# JustStupid.net
KiCad netlist of a schematic drawn in EAGLE
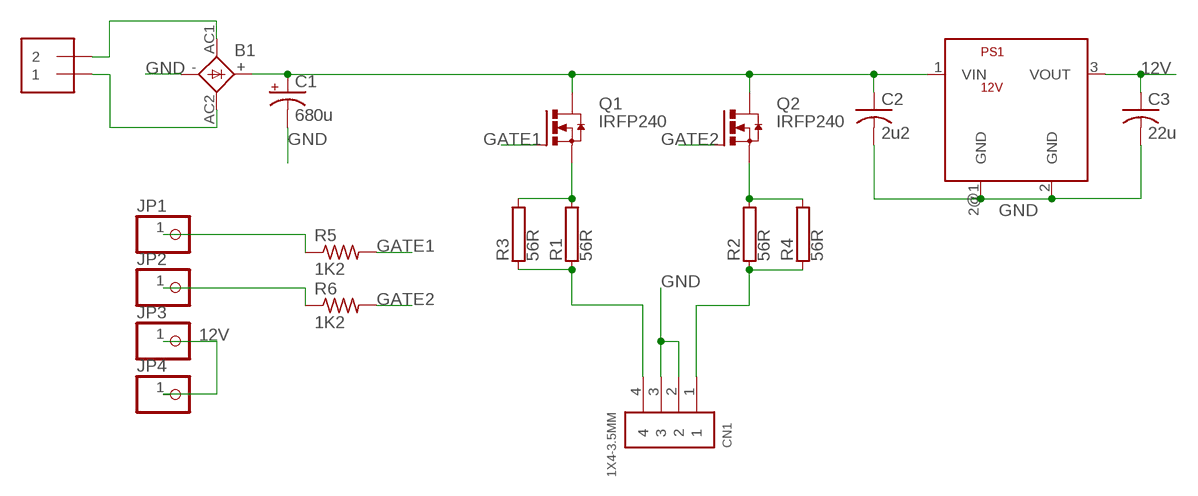
[diagram p0: schematic, sheet 1]

(export (version "E")
  (design (tool "Eeschema 10.0.6"))
  (components
    (comp (ref "ACIN")
      (value "1X2-3.5MM")
      (footprint "eagle-import:1X2-3.5MM")
      (libsource (lib "eagle-import") (part "1X2-3.5MM"))
    )
    (comp (ref "B1")
      (value "KBU")
      (footprint "eagle-import:KBU")
      (libsource (lib "eagle-import") (part "KBU"))
    )
    (comp (ref "C1")
      (value "680u")
      (footprint "eagle-import:PCPIN_CAP")
      (libsource (lib "eagle-import") (part "C_POL"))
    )
    (comp (ref "C2")
      (value "2u2")
      (footprint "eagle-import:C2220K")
      (libsource (lib "eagle-import") (part "C-USC2220K"))
    )
    (comp (ref "C3")
      (value "22u")
      (footprint "eagle-import:C1206")
      (libsource (lib "eagle-import") (part "C-USC1206"))
    )
    (comp (ref "CN1")
      (value "1X4-3.5MM")
      (footprint "eagle-import:1X04-3.5MM")
      (libsource (lib "eagle-import") (part "1X4-3.5MM"))
    )
    (comp (ref "JP1")
      (value "PINHD-1X1")
      (footprint "eagle-import:1X01")
      (libsource (lib "eagle-import") (part "PINHD-1X1"))
    )
    (comp (ref "JP2")
      (value "PINHD-1X1")
      (footprint "eagle-import:1X01")
      (libsource (lib "eagle-import") (part "PINHD-1X1"))
    )
    (comp (ref "JP3")
      (value "PINHD-1X1")
      (footprint "eagle-import:1X01")
      (libsource (lib "eagle-import") (part "PINHD-1X1"))
    )
    (comp (ref "JP4")
      (value "PINHD-1X1")
      (footprint "eagle-import:1X01")
      (libsource (lib "eagle-import") (part "PINHD-1X1"))
    )
    (comp (ref "PS1")
      (value "12V")
      (footprint "eagle-import:SOT89")
      (libsource (lib "eagle-import") (part "NCP785A"))
    )
    (comp (ref "Q1")
      (value "IRFP240")
      (footprint "eagle-import:TO247BV")
      (libsource (lib "eagle-import") (part "IRFP240"))
    )
    (comp (ref "Q2")
      (value "IRFP240")
      (footprint "eagle-import:TO247BV")
      (libsource (lib "eagle-import") (part "IRFP240"))
    )
    (comp (ref "R1")
      (value "56R")
      (footprint "eagle-import:TO-247-2V")
      (libsource (lib "eagle-import") (part "RMG100-V"))
    )
    (comp (ref "R2")
      (value "56R")
      (footprint "eagle-import:TO-247-2V")
      (libsource (lib "eagle-import") (part "RMG100-V"))
    )
    (comp (ref "R3")
      (value "56R")
      (footprint "eagle-import:TO-247-2V")
      (libsource (lib "eagle-import") (part "RMG100-V"))
    )
    (comp (ref "R4")
      (value "56R")
      (footprint "eagle-import:TO-247-2V")
      (libsource (lib "eagle-import") (part "RMG100-V"))
    )
    (comp (ref "R5")
      (value "1K2")
      (footprint "eagle-import:R1206")
      (libsource (lib "eagle-import") (part "R-US_R1206"))
    )
    (comp (ref "R6")
      (value "1K2")
      (footprint "eagle-import:R1206")
      (libsource (lib "eagle-import") (part "R-US_R1206"))
    )
  )
  (nets
    (net (code "1") (name "/12V") (class "Default")
      (node (ref "C3") (pin "1") (pinfunction "1_1") (pintype "passive"))
      (node (ref "JP3") (pin "1") (pinfunction "1_1") (pintype "passive"))
      (node (ref "JP4") (pin "1") (pinfunction "1_1") (pintype "passive"))
      (node (ref "PS1") (pin "3") (pinfunction "VOUT_3") (pintype "bidirectional"))
    )
    (net (code "2") (name "/GATE1") (class "Default")
      (node (ref "Q1") (pin "G") (pinfunction "G_G") (pintype "passive"))
      (node (ref "R5") (pin "2") (pinfunction "2_2") (pintype "passive"))
    )
    (net (code "3") (name "/GATE2") (class "Default")
      (node (ref "Q2") (pin "G") (pinfunction "G_G") (pintype "passive"))
      (node (ref "R6") (pin "2") (pinfunction "2_2") (pintype "passive"))
    )
    (net (code "4") (name "/GND") (class "Default")
      (node (ref "B1") (pin "-") (pinfunction "-_-") (pintype "passive"))
      (node (ref "C1") (pin "P$1") (pinfunction "-_P$1") (pintype "passive"))
      (node (ref "C2") (pin "2") (pinfunction "2_2") (pintype "passive"))
      (node (ref "C3") (pin "2") (pinfunction "2_2") (pintype "passive"))
      (node (ref "CN1") (pin "2") (pinfunction "2_2") (pintype "bidirectional"))
      (node (ref "CN1") (pin "3") (pinfunction "3_3") (pintype "bidirectional"))
      (node (ref "PS1") (pin "2") (pinfunction "GND_2") (pintype "bidirectional"))
      (node (ref "PS1") (pin "2@1") (pinfunction "GND_2@1") (pintype "bidirectional"))
    )
    (net (code "5") (name "Net-(ACIN-Pad1)") (class "Default")
      (node (ref "ACIN") (pin "1") (pinfunction "1_1") (pintype "passive"))
      (node (ref "B1") (pin "AC2") (pinfunction "AC2_AC2") (pintype "passive"))
    )
    (net (code "6") (name "Net-(ACIN-Pad2)") (class "Default")
      (node (ref "ACIN") (pin "2") (pinfunction "2_2") (pintype "passive"))
      (node (ref "B1") (pin "AC1") (pinfunction "AC1_AC1") (pintype "passive"))
    )
    (net (code "7") (name "Net-(C1-+)") (class "Default")
      (node (ref "B1") (pin "+") (pinfunction "+_+") (pintype "passive"))
      (node (ref "C1") (pin "P$2") (pinfunction "+_P$2") (pintype "passive"))
      (node (ref "C2") (pin "1") (pinfunction "1_1") (pintype "passive"))
      (node (ref "PS1") (pin "1") (pinfunction "VIN_1") (pintype "bidirectional"))
      (node (ref "Q1") (pin "D") (pinfunction "D_D") (pintype "passive"))
      (node (ref "Q2") (pin "D") (pinfunction "D_D") (pintype "passive"))
    )
    (net (code "8") (name "Net-(CN1-Pad1)") (class "Default")
      (node (ref "CN1") (pin "1") (pinfunction "1_1") (pintype "bidirectional"))
      (node (ref "R2") (pin "1") (pinfunction "1_1") (pintype "passive"))
      (node (ref "R4") (pin "1") (pinfunction "1_1") (pintype "passive"))
    )
    (net (code "9") (name "Net-(CN1-Pad4)") (class "Default")
      (node (ref "CN1") (pin "4") (pinfunction "4_4") (pintype "bidirectional"))
      (node (ref "R1") (pin "1") (pinfunction "1_1") (pintype "passive"))
      (node (ref "R3") (pin "1") (pinfunction "1_1") (pintype "passive"))
    )
    (net (code "10") (name "Net-(JP1-Pad1)") (class "Default")
      (node (ref "JP1") (pin "1") (pinfunction "1_1") (pintype "passive"))
      (node (ref "R5") (pin "1") (pinfunction "1_1") (pintype "passive"))
    )
    (net (code "11") (name "Net-(JP2-Pad1)") (class "Default")
      (node (ref "JP2") (pin "1") (pinfunction "1_1") (pintype "passive"))
      (node (ref "R6") (pin "1") (pinfunction "1_1") (pintype "passive"))
    )
    (net (code "12") (name "Net-(Q1-PadS)") (class "Default")
      (node (ref "Q1") (pin "S") (pinfunction "S_S") (pintype "passive"))
      (node (ref "R1") (pin "2") (pinfunction "2_2") (pintype "passive"))
      (node (ref "R3") (pin "2") (pinfunction "2_2") (pintype "passive"))
    )
    (net (code "13") (name "Net-(Q2-PadS)") (class "Default")
      (node (ref "Q2") (pin "S") (pinfunction "S_S") (pintype "passive"))
      (node (ref "R2") (pin "2") (pinfunction "2_2") (pintype "passive"))
      (node (ref "R4") (pin "2") (pinfunction "2_2") (pintype "passive"))
    )
  )
)
